# mixer-L-band-MAC-24.net
KiCad netlist of a schematic drawn in EAGLE
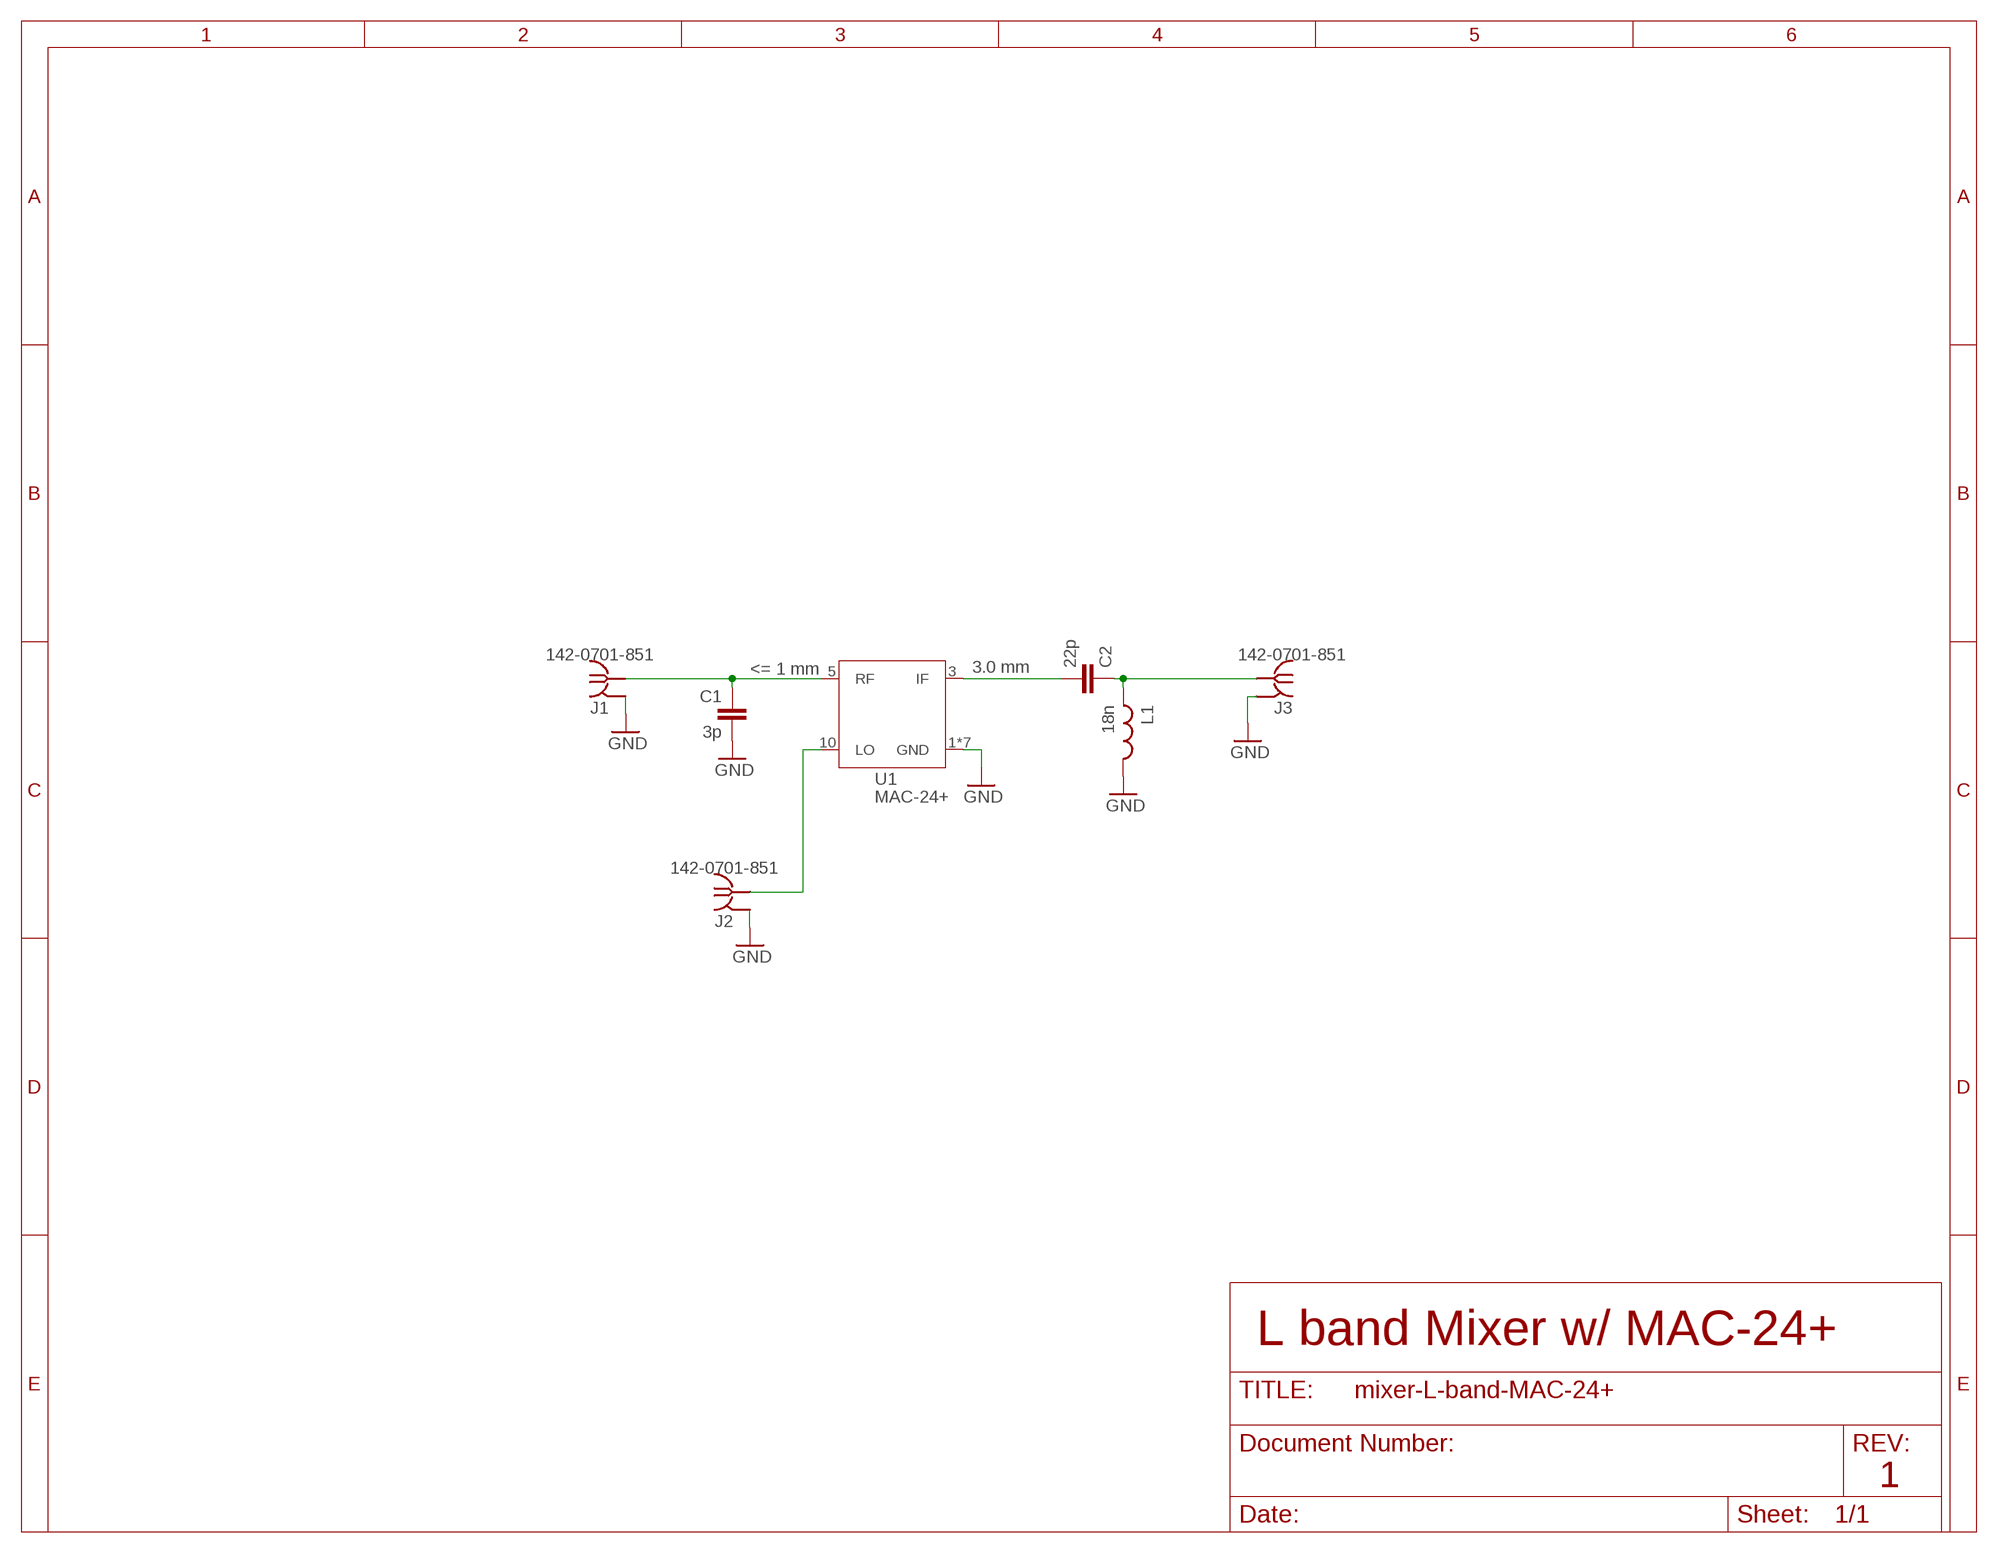
[diagram p0: schematic, sheet 1]

(export (version "E")
  (design (tool "Eeschema 10.0.6"))
  (components
    (comp (ref "C1")
      (value "3p")
      (footprint "eagle-import:.0402-B-NOSILK")
      (libsource (lib "eagle-import") (part "C-EU0402-B-NOSILK"))
    )
    (comp (ref "C2")
      (value "22p")
      (footprint "eagle-import:.0402-B-NOSILK")
      (libsource (lib "eagle-import") (part "C-EU0402-B-NOSILK"))
    )
    (comp (ref "J1")
      (value "142-0701-851")
      (footprint "eagle-import:142-0701-851")
      (libsource (lib "eagle-import") (part "142-0701-851"))
    )
    (comp (ref "J2")
      (value "142-0701-851")
      (footprint "eagle-import:142-0701-851")
      (libsource (lib "eagle-import") (part "142-0701-851"))
    )
    (comp (ref "J3")
      (value "142-0701-851")
      (footprint "eagle-import:142-0701-851")
      (libsource (lib "eagle-import") (part "142-0701-851"))
    )
    (comp (ref "L1")
      (value "18n")
      (footprint "eagle-import:.0402-B-NOSILK")
      (libsource (lib "eagle-import") (part "L-US0402-B-NOSILK"))
    )
    (comp (ref "U1")
      (value "MAC-24+")
      (footprint "eagle-import:MAC-24+")
      (libsource (lib "eagle-import") (part "MAC-24+"))
    )
  )
  (nets
    (net (code "1") (name "GND") (class "Default")
      (node (ref "C1") (pin "2") (pinfunction "2_2") (pintype "passive"))
      (node (ref "J1") (pin "GND1") (pinfunction "GND_GND1") (pintype "bidirectional"))
      (node (ref "J1") (pin "GND2") (pinfunction "GND_GND2") (pintype "bidirectional"))
      (node (ref "J1") (pin "GND3") (pinfunction "GND_GND3") (pintype "bidirectional"))
      (node (ref "J1") (pin "GND4") (pinfunction "GND_GND4") (pintype "bidirectional"))
      (node (ref "J2") (pin "GND1") (pinfunction "GND_GND1") (pintype "bidirectional"))
      (node (ref "J2") (pin "GND2") (pinfunction "GND_GND2") (pintype "bidirectional"))
      (node (ref "J2") (pin "GND3") (pinfunction "GND_GND3") (pintype "bidirectional"))
      (node (ref "J2") (pin "GND4") (pinfunction "GND_GND4") (pintype "bidirectional"))
      (node (ref "J3") (pin "GND1") (pinfunction "GND_GND1") (pintype "bidirectional"))
      (node (ref "J3") (pin "GND2") (pinfunction "GND_GND2") (pintype "bidirectional"))
      (node (ref "J3") (pin "GND3") (pinfunction "GND_GND3") (pintype "bidirectional"))
      (node (ref "J3") (pin "GND4") (pinfunction "GND_GND4") (pintype "bidirectional"))
      (node (ref "L1") (pin "2") (pinfunction "2_2") (pintype "passive"))
      (node (ref "U1") (pin "1") (pinfunction "GND_1") (pintype "power_in"))
      (node (ref "U1") (pin "2") (pinfunction "GND_2") (pintype "power_in"))
      (node (ref "U1") (pin "4") (pinfunction "GND_4") (pintype "power_in"))
      (node (ref "U1") (pin "6") (pinfunction "GND_6") (pintype "power_in"))
      (node (ref "U1") (pin "7") (pinfunction "GND_7") (pintype "power_in"))
      (node (ref "U1") (pin "8") (pinfunction "GND_8") (pintype "power_in"))
      (node (ref "U1") (pin "9") (pinfunction "GND_9") (pintype "power_in"))
    )
    (net (code "2") (name "Net-(J1-RF)") (class "Default")
      (node (ref "C1") (pin "1") (pinfunction "1_1") (pintype "passive"))
      (node (ref "J1") (pin "RF1") (pinfunction "RF_RF1") (pintype "bidirectional"))
      (node (ref "U1") (pin "5") (pinfunction "RF_5") (pintype "input"))
    )
    (net (code "3") (name "Net-(J2-RF)") (class "Default")
      (node (ref "J2") (pin "RF1") (pinfunction "RF_RF1") (pintype "bidirectional"))
      (node (ref "U1") (pin "10") (pinfunction "LO_10") (pintype "input"))
    )
    (net (code "4") (name "Net-(J3-RF)") (class "Default")
      (node (ref "C2") (pin "1") (pinfunction "1_1") (pintype "passive"))
      (node (ref "J3") (pin "RF1") (pinfunction "RF_RF1") (pintype "bidirectional"))
      (node (ref "L1") (pin "1") (pinfunction "1_1") (pintype "passive"))
    )
    (net (code "5") (name "Net-(U1-IF)") (class "Default")
      (node (ref "C2") (pin "2") (pinfunction "2_2") (pintype "passive"))
      (node (ref "U1") (pin "3") (pinfunction "IF_3") (pintype "output"))
    )
  )
)
